# AMS_temperature.net
KiCad netlist of a schematic drawn in Altium Designer
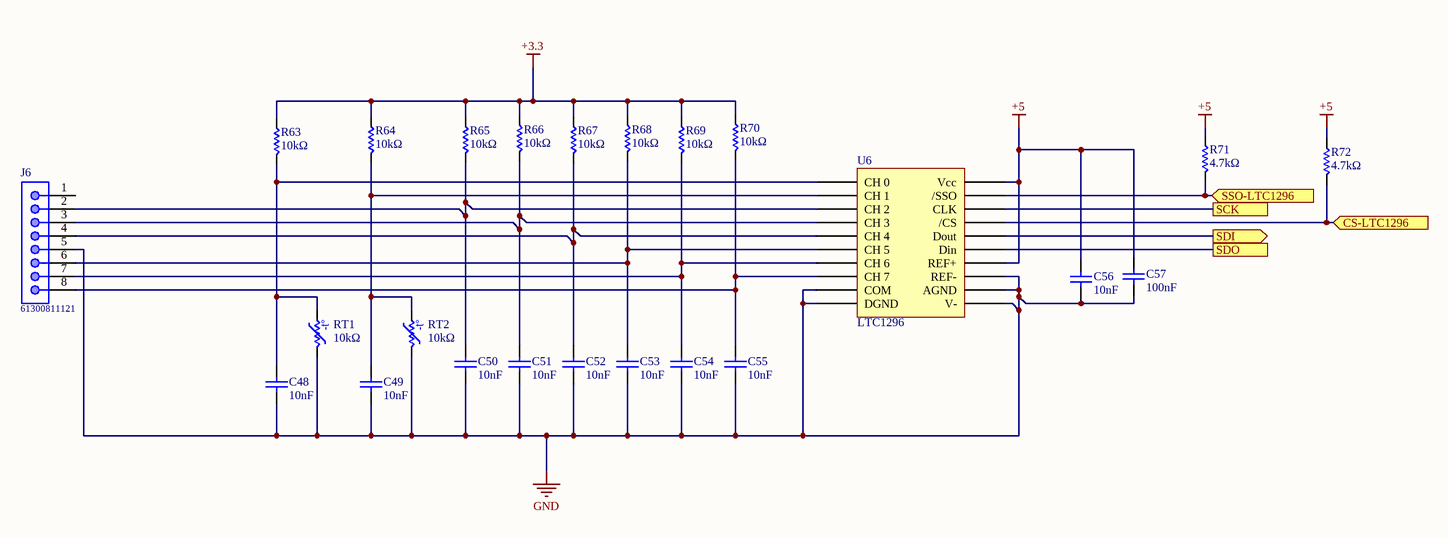
[diagram p0: AMS_temperature.SchDoc]

(export (version "E")
  (design (tool "Eeschema 10.0.6"))
  (components
    (comp (ref "C48")
      (value "10nF")
      (footprint "0805_2x1.25x0.8mm_Reflow Soldering")
      (description "WCAP-CSGP Ceramic Capacitors, 0805, X7R, 50V, 10nF")
      (fields (field (name "PART NUMBER") "885012207092") (field (name "PUBLISHER") "Wurth Elektronik"))
      (libsource (lib "Components_Library") (part "885012207092"))
    )
    (comp (ref "C49")
      (value "10nF")
      (footprint "0805_2x1.25x0.8mm_Reflow Soldering")
      (description "WCAP-CSGP Ceramic Capacitors, 0805, X7R, 50V, 10nF")
      (fields (field (name "PART NUMBER") "885012207092") (field (name "PUBLISHER") "Wurth Elektronik"))
      (libsource (lib "Components_Library") (part "885012207092"))
    )
    (comp (ref "C50")
      (value "10nF")
      (footprint "0805_2x1.25x0.8mm_Reflow Soldering")
      (description "WCAP-CSGP Ceramic Capacitors, 0805, X7R, 50V, 10nF")
      (fields (field (name "PART NUMBER") "885012207092") (field (name "PUBLISHER") "Wurth Elektronik"))
      (libsource (lib "Components_Library") (part "885012207092"))
    )
    (comp (ref "C51")
      (value "10nF")
      (footprint "0805_2x1.25x0.8mm_Reflow Soldering")
      (description "WCAP-CSGP Ceramic Capacitors, 0805, X7R, 50V, 10nF")
      (fields (field (name "PART NUMBER") "885012207092") (field (name "PUBLISHER") "Wurth Elektronik"))
      (libsource (lib "Components_Library") (part "885012207092"))
    )
    (comp (ref "C52")
      (value "10nF")
      (footprint "0805_2x1.25x0.8mm_Reflow Soldering")
      (description "WCAP-CSGP Ceramic Capacitors, 0805, X7R, 50V, 10nF")
      (fields (field (name "PART NUMBER") "885012207092") (field (name "PUBLISHER") "Wurth Elektronik"))
      (libsource (lib "Components_Library") (part "885012207092"))
    )
    (comp (ref "C53")
      (value "10nF")
      (footprint "0805_2x1.25x0.8mm_Reflow Soldering")
      (description "WCAP-CSGP Ceramic Capacitors, 0805, X7R, 50V, 10nF")
      (fields (field (name "PART NUMBER") "885012207092") (field (name "PUBLISHER") "Wurth Elektronik"))
      (libsource (lib "Components_Library") (part "885012207092"))
    )
    (comp (ref "C54")
      (value "10nF")
      (footprint "0805_2x1.25x0.8mm_Reflow Soldering")
      (description "WCAP-CSGP Ceramic Capacitors, 0805, X7R, 50V, 10nF")
      (fields (field (name "PART NUMBER") "885012207092") (field (name "PUBLISHER") "Wurth Elektronik"))
      (libsource (lib "Components_Library") (part "885012207092"))
    )
    (comp (ref "C55")
      (value "10nF")
      (footprint "0805_2x1.25x0.8mm_Reflow Soldering")
      (description "WCAP-CSGP Ceramic Capacitors, 0805, X7R, 50V, 10nF")
      (fields (field (name "PART NUMBER") "885012207092") (field (name "PUBLISHER") "Wurth Elektronik"))
      (libsource (lib "Components_Library") (part "885012207092"))
    )
    (comp (ref "C56")
      (value "10nF")
      (footprint "0805_2x1.25x0.8mm_Reflow Soldering")
      (description "WCAP-CSGP Ceramic Capacitors, 0805, X7R, 50V, 10nF")
      (fields (field (name "PART NUMBER") "885012207092") (field (name "PUBLISHER") "Wurth Elektronik"))
      (libsource (lib "Components_Library") (part "885012207092"))
    )
    (comp (ref "C57")
      (value "100nF")
      (footprint "0805_2x1.25x0.8mm_Reflow Soldering")
      (description "WCAP-CSGP Ceramic Capacitors, 0805, X7R, 50V, 100nF")
      (fields (field (name "PART NUMBER") "885012207098") (field (name "PUBLISHER") "Wurth Elektronik"))
      (libsource (lib "Components_Library") (part "885012207098"))
    )
    (comp (ref "J6")
      (value "61300811121")
      (footprint "61300811121-bottom")
      (description "THT Vertical Pin Header WR-PHD, Pitch 2.54 mm, Single Row, 8 pins")
      (fields (field (name "PUBLISHER") "Wurth Elektronik"))
      (libsource (lib "Components_Library") (part "61300811121"))
    )
    (comp (ref "R63")
      (value "10kΩ")
      (footprint "CR0805")
      (description "Chip Resistor 0805")
      (fields (field (name "MANUFACTURER") "Bourns"))
      (libsource (lib "Components_Library") (part "CR0805-JW-103ELF"))
    )
    (comp (ref "R64")
      (value "10kΩ")
      (footprint "CR0805")
      (description "Chip Resistor 0805")
      (fields (field (name "MANUFACTURER") "Bourns"))
      (libsource (lib "Components_Library") (part "CR0805-JW-103ELF"))
    )
    (comp (ref "R65")
      (value "10kΩ")
      (footprint "CR0805")
      (description "Chip Resistor 0805")
      (fields (field (name "MANUFACTURER") "Bourns"))
      (libsource (lib "Components_Library") (part "CR0805-JW-103ELF"))
    )
    (comp (ref "R66")
      (value "10kΩ")
      (footprint "CR0805")
      (description "Chip Resistor 0805")
      (fields (field (name "MANUFACTURER") "Bourns"))
      (libsource (lib "Components_Library") (part "CR0805-JW-103ELF"))
    )
    (comp (ref "R67")
      (value "10kΩ")
      (footprint "CR0805")
      (description "Chip Resistor 0805")
      (fields (field (name "MANUFACTURER") "Bourns"))
      (libsource (lib "Components_Library") (part "CR0805-JW-103ELF"))
    )
    (comp (ref "R68")
      (value "10kΩ")
      (footprint "CR0805")
      (description "Chip Resistor 0805")
      (fields (field (name "MANUFACTURER") "Bourns"))
      (libsource (lib "Components_Library") (part "CR0805-JW-103ELF"))
    )
    (comp (ref "R69")
      (value "10kΩ")
      (footprint "CR0805")
      (description "Chip Resistor 0805")
      (fields (field (name "MANUFACTURER") "Bourns"))
      (libsource (lib "Components_Library") (part "CR0805-JW-103ELF"))
    )
    (comp (ref "R70")
      (value "10kΩ")
      (footprint "CR0805")
      (description "Chip Resistor 0805")
      (fields (field (name "MANUFACTURER") "Bourns"))
      (libsource (lib "Components_Library") (part "CR0805-JW-103ELF"))
    )
    (comp (ref "R71")
      (value "4.7kΩ")
      (footprint "CR0805")
      (description "Chip Resistor 0805")
      (fields (field (name "MANUFACTURER") "Bourns"))
      (libsource (lib "Components_Library") (part "CR0805-FX-4701GLF"))
    )
    (comp (ref "R72")
      (value "4.7kΩ")
      (footprint "CR0805")
      (description "Chip Resistor 0805")
      (fields (field (name "MANUFACTURER") "Bourns"))
      (libsource (lib "Components_Library") (part "CR0805-FX-4701GLF"))
    )
    (comp (ref "RT1")
      (value "10kΩ")
      (footprint "NXRT15XV103FA1B040")
      (description "NTC Thermistor Leaded type NXRT Series")
      (fields (field (name "MANUFACTURER") "Murata"))
      (libsource (lib "Components_Library") (part "NXRT15XV103FA1B040"))
    )
    (comp (ref "RT2")
      (value "10kΩ")
      (footprint "NXRT15XV103FA1B040")
      (description "NTC Thermistor Leaded type NXRT Series")
      (fields (field (name "MANUFACTURER") "Murata"))
      (libsource (lib "Components_Library") (part "NXRT15XV103FA1B040"))
    )
    (comp (ref "U6")
      (value "LTC1296")
      (footprint "LTC1296")
      (description "ADC. Single Chip 12-Bit Data Acquisition System.")
      (fields (field (name "MANUFACTURER") "Linear"))
      (libsource (lib "Components_Library") (part "LTC1296"))
    )
  )
  (nets
    (net (code "1") (name "+3.3") (class "Default")
      (node (ref "R63") (pin "2") (pinfunction "2_2") (pintype "passive"))
      (node (ref "R64") (pin "2") (pinfunction "2_2") (pintype "passive"))
      (node (ref "R65") (pin "2") (pinfunction "2_2") (pintype "passive"))
      (node (ref "R66") (pin "2") (pinfunction "2_2") (pintype "passive"))
      (node (ref "R67") (pin "2") (pinfunction "2_2") (pintype "passive"))
      (node (ref "R68") (pin "2") (pinfunction "2_2") (pintype "passive"))
      (node (ref "R69") (pin "2") (pinfunction "2_2") (pintype "passive"))
      (node (ref "R70") (pin "2") (pinfunction "2_2") (pintype "passive"))
    )
    (net (code "2") (name "+5") (class "Default")
      (node (ref "C56") (pin "2") (pinfunction "2_2") (pintype "passive"))
      (node (ref "C57") (pin "2") (pinfunction "2_2") (pintype "passive"))
      (node (ref "R71") (pin "2") (pinfunction "2_2") (pintype "passive"))
      (node (ref "R72") (pin "2") (pinfunction "2_2") (pintype "passive"))
      (node (ref "U6") (pin "14") (pinfunction "REF+_14") (pintype "passive"))
      (node (ref "U6") (pin "20") (pinfunction "Vcc_20") (pintype "passive"))
    )
    (net (code "3") (name "/CS-LTC1296") (class "Default")
      (node (ref "R72") (pin "1") (pinfunction "1_1") (pintype "passive"))
      (node (ref "U6") (pin "17") (pinfunction "/CS_17") (pintype "passive"))
    )
    (net (code "4") (name "/SCK") (class "Default")
      (node (ref "U6") (pin "18") (pinfunction "CLK_18") (pintype "passive"))
    )
    (net (code "5") (name "/SDI") (class "Default")
      (node (ref "U6") (pin "16") (pinfunction "Dout_16") (pintype "passive"))
    )
    (net (code "6") (name "/SDO") (class "Default")
      (node (ref "U6") (pin "15") (pinfunction "Din_15") (pintype "passive"))
    )
    (net (code "7") (name "/SSO-LTC1296") (class "Default")
      (node (ref "R71") (pin "1") (pinfunction "1_1") (pintype "passive"))
      (node (ref "U6") (pin "19") (pinfunction "/SSO_19") (pintype "passive"))
    )
    (net (code "8") (name "GND") (class "Default")
      (node (ref "C48") (pin "1") (pinfunction "1_1") (pintype "passive"))
      (node (ref "C49") (pin "1") (pinfunction "1_1") (pintype "passive"))
      (node (ref "C50") (pin "1") (pinfunction "1_1") (pintype "passive"))
      (node (ref "C51") (pin "1") (pinfunction "1_1") (pintype "passive"))
      (node (ref "C52") (pin "1") (pinfunction "1_1") (pintype "passive"))
      (node (ref "C53") (pin "1") (pinfunction "1_1") (pintype "passive"))
      (node (ref "C54") (pin "1") (pinfunction "1_1") (pintype "passive"))
      (node (ref "C55") (pin "1") (pinfunction "1_1") (pintype "passive"))
      (node (ref "C56") (pin "1") (pinfunction "1_1") (pintype "passive"))
      (node (ref "C57") (pin "1") (pinfunction "1_1") (pintype "passive"))
      (node (ref "J6") (pin "5") (pinfunction "5_5") (pintype "passive"))
      (node (ref "RT1") (pin "1") (pinfunction "1_1") (pintype "passive"))
      (node (ref "RT2") (pin "1") (pinfunction "1_1") (pintype "passive"))
      (node (ref "U6") (pin "10") (pinfunction "DGND_10") (pintype "passive"))
      (node (ref "U6") (pin "11") (pinfunction "V-_11") (pintype "passive"))
      (node (ref "U6") (pin "12") (pinfunction "AGND_12") (pintype "passive"))
      (node (ref "U6") (pin "13") (pinfunction "REF-_13") (pintype "passive"))
      (node (ref "U6") (pin "9") (pinfunction "COM_9") (pintype "passive"))
    )
    (net (code "9") (name "Net-(U6-CH_0)") (class "Default")
      (node (ref "C48") (pin "2") (pinfunction "2_2") (pintype "passive"))
      (node (ref "R63") (pin "1") (pinfunction "1_1") (pintype "passive"))
      (node (ref "RT1") (pin "2") (pinfunction "2_2") (pintype "passive"))
      (node (ref "U6") (pin "1") (pinfunction "CH_0_1") (pintype "passive"))
    )
    (net (code "10") (name "Net-(U6-CH_1)") (class "Default")
      (node (ref "C49") (pin "2") (pinfunction "2_2") (pintype "passive"))
      (node (ref "R64") (pin "1") (pinfunction "1_1") (pintype "passive"))
      (node (ref "RT2") (pin "2") (pinfunction "2_2") (pintype "passive"))
      (node (ref "U6") (pin "2") (pinfunction "CH_1_2") (pintype "passive"))
    )
    (net (code "11") (name "Net-(U6-CH_2)") (class "Default")
      (node (ref "C50") (pin "2") (pinfunction "2_2") (pintype "passive"))
      (node (ref "J6") (pin "2") (pinfunction "2_2") (pintype "passive"))
      (node (ref "R65") (pin "1") (pinfunction "1_1") (pintype "passive"))
      (node (ref "U6") (pin "3") (pinfunction "CH_2_3") (pintype "passive"))
    )
    (net (code "12") (name "Net-(U6-CH_3)") (class "Default")
      (node (ref "C51") (pin "2") (pinfunction "2_2") (pintype "passive"))
      (node (ref "J6") (pin "3") (pinfunction "3_3") (pintype "passive"))
      (node (ref "R66") (pin "1") (pinfunction "1_1") (pintype "passive"))
      (node (ref "U6") (pin "4") (pinfunction "CH_3_4") (pintype "passive"))
    )
    (net (code "13") (name "Net-(U6-CH_4)") (class "Default")
      (node (ref "C52") (pin "2") (pinfunction "2_2") (pintype "passive"))
      (node (ref "J6") (pin "4") (pinfunction "4_4") (pintype "passive"))
      (node (ref "R67") (pin "1") (pinfunction "1_1") (pintype "passive"))
      (node (ref "U6") (pin "5") (pinfunction "CH_4_5") (pintype "passive"))
    )
    (net (code "14") (name "Net-(U6-CH_5)") (class "Default")
      (node (ref "C53") (pin "2") (pinfunction "2_2") (pintype "passive"))
      (node (ref "J6") (pin "6") (pinfunction "6_6") (pintype "passive"))
      (node (ref "R68") (pin "1") (pinfunction "1_1") (pintype "passive"))
      (node (ref "U6") (pin "6") (pinfunction "CH_5_6") (pintype "passive"))
    )
    (net (code "15") (name "Net-(U6-CH_6)") (class "Default")
      (node (ref "C54") (pin "2") (pinfunction "2_2") (pintype "passive"))
      (node (ref "J6") (pin "7") (pinfunction "7_7") (pintype "passive"))
      (node (ref "R69") (pin "1") (pinfunction "1_1") (pintype "passive"))
      (node (ref "U6") (pin "7") (pinfunction "CH_6_7") (pintype "passive"))
    )
    (net (code "16") (name "Net-(U6-CH_7)") (class "Default")
      (node (ref "C55") (pin "2") (pinfunction "2_2") (pintype "passive"))
      (node (ref "J6") (pin "8") (pinfunction "8_8") (pintype "passive"))
      (node (ref "R70") (pin "1") (pinfunction "1_1") (pintype "passive"))
      (node (ref "U6") (pin "8") (pinfunction "CH_7_8") (pintype "passive"))
    )
    (net (code "17") (name "unconnected-(J6-Pad1)") (class "Default")
      (node (ref "J6") (pin "1") (pinfunction "1_1") (pintype "passive"))
    )
  )
)
